# 11_JNZ.net
KiCad netlist of a schematic drawn in EAGLE
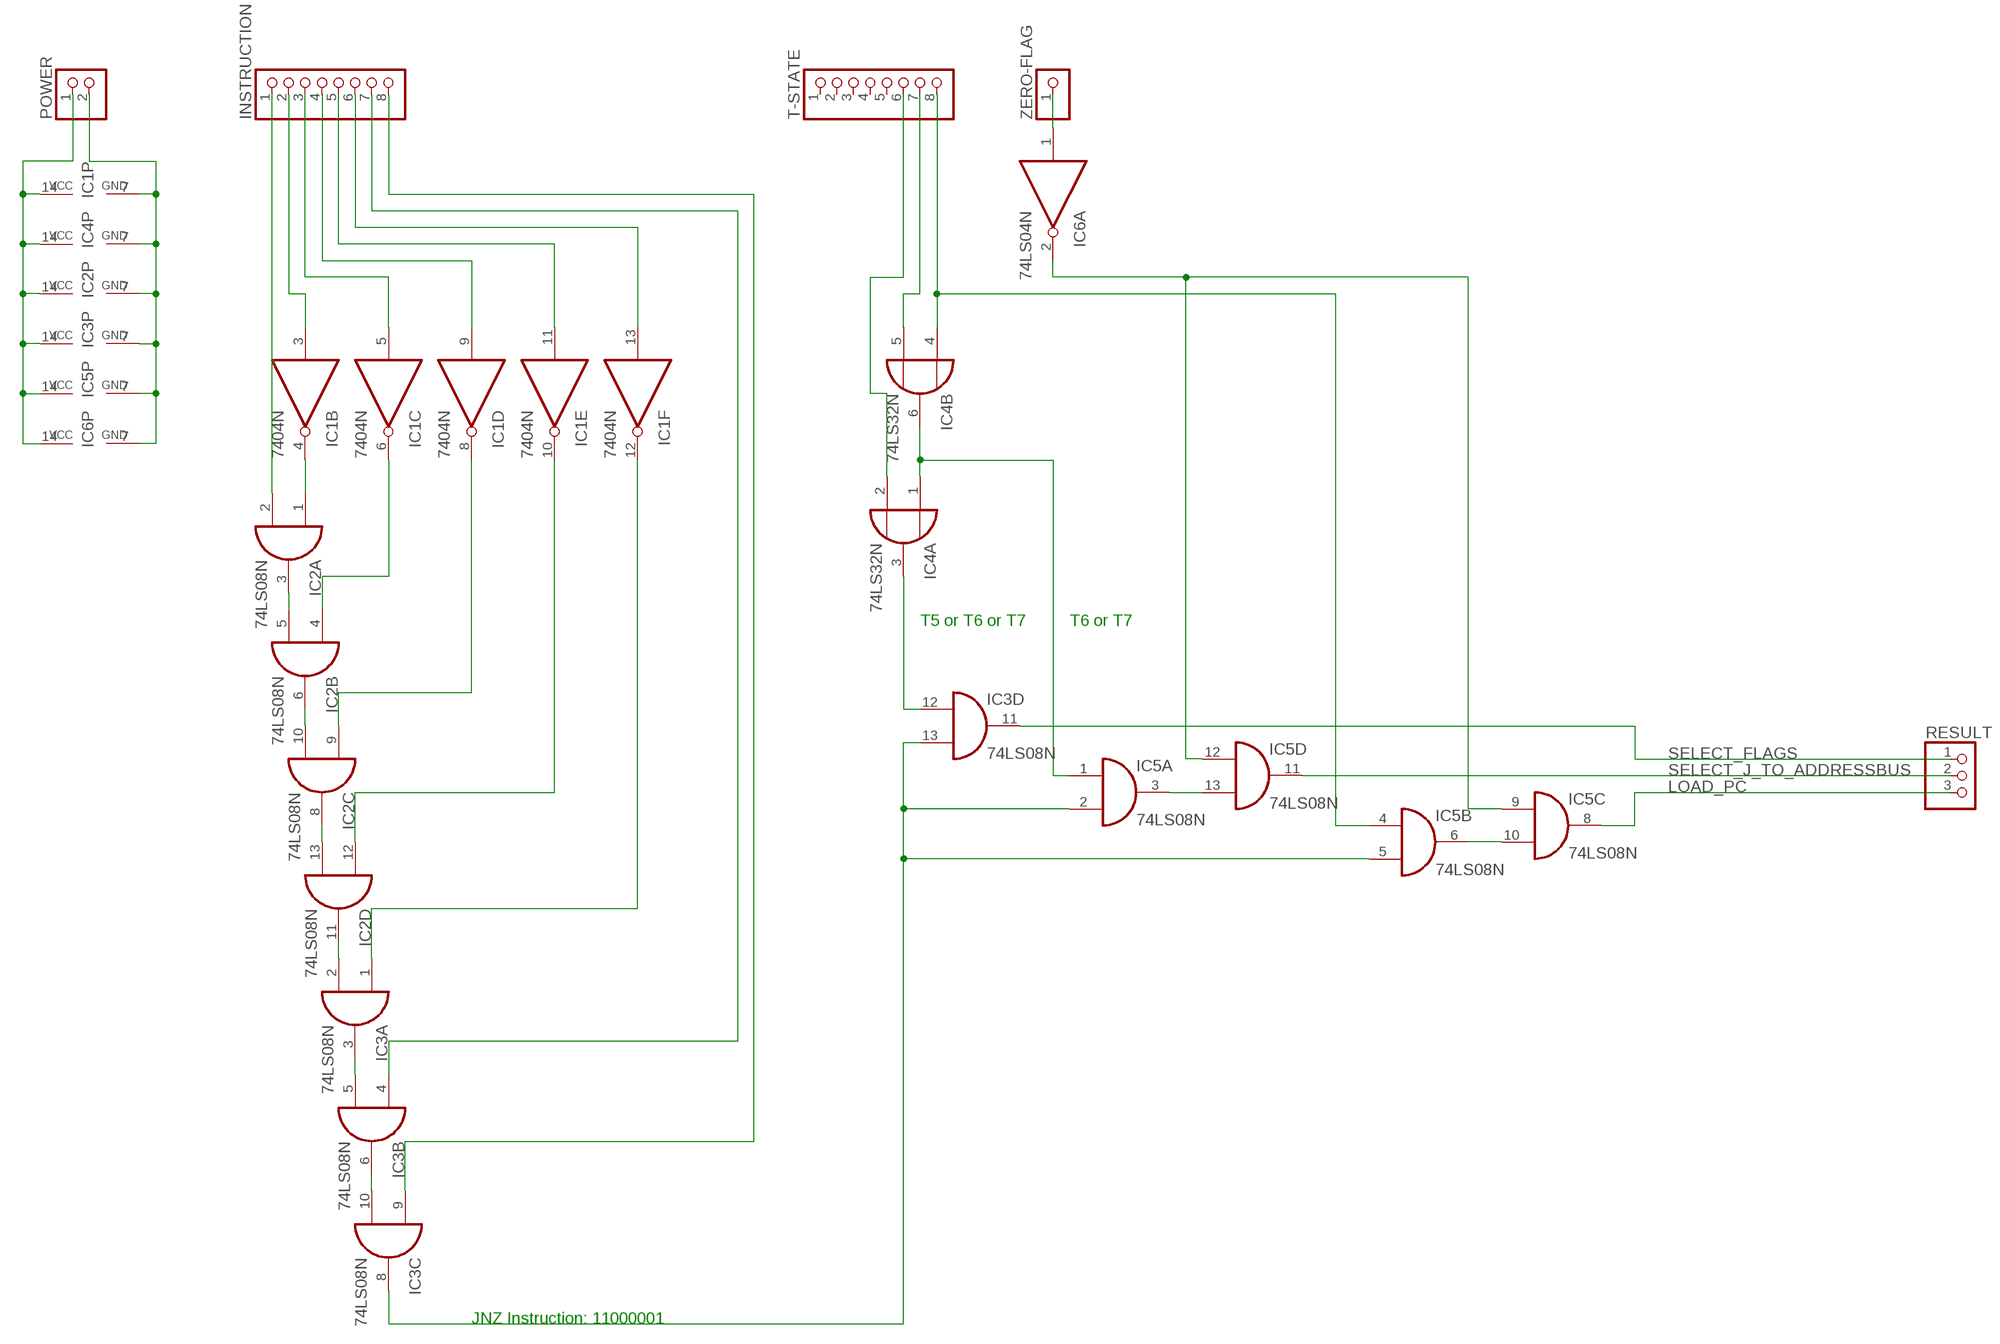
[diagram p0: schematic, sheet 1]

(export (version "E")
  (design (tool "Eeschema 10.0.6"))
  (components
    (comp (ref "IC1")
      (value "7404N")
      (footprint "eagle-import:DIL14")
      (libsource (lib "eagle-import") (part "7404N"))
    )
    (comp (ref "IC2")
      (value "74LS08N")
      (footprint "eagle-import:DIL14")
      (libsource (lib "eagle-import") (part "7408NLS"))
    )
    (comp (ref "IC3")
      (value "74LS08N")
      (footprint "eagle-import:DIL14")
      (libsource (lib "eagle-import") (part "7408NLS"))
    )
    (comp (ref "IC4")
      (value "74LS32N")
      (footprint "eagle-import:DIL14")
      (libsource (lib "eagle-import") (part "7432NLS"))
    )
    (comp (ref "IC5")
      (value "74LS08N")
      (footprint "eagle-import:DIL14")
      (libsource (lib "eagle-import") (part "7408NLS"))
    )
    (comp (ref "IC6")
      (value "74LS04N")
      (footprint "eagle-import:DIL14")
      (libsource (lib "eagle-import") (part "7404NLS"))
    )
    (comp (ref "INSTRUCTION")
      (value "PINHD-1X8")
      (footprint "eagle-import:1X08")
      (libsource (lib "eagle-import") (part "PINHD-1X8"))
    )
    (comp (ref "POWER")
      (value "PINHD-1X2")
      (footprint "eagle-import:1X02")
      (libsource (lib "eagle-import") (part "PINHD-1X2"))
    )
    (comp (ref "RESULT")
      (value "PINHD-1X3")
      (footprint "eagle-import:1X03")
      (libsource (lib "eagle-import") (part "PINHD-1X3"))
    )
    (comp (ref "T-STATE")
      (value "PINHD-1X8")
      (footprint "eagle-import:1X08")
      (libsource (lib "eagle-import") (part "PINHD-1X8"))
    )
    (comp (ref "ZERO-FLAG")
      (value "PINHD-1X1")
      (footprint "eagle-import:1X01")
      (libsource (lib "eagle-import") (part "PINHD-1X1"))
    )
  )
  (nets
    (net (code "1") (name "/LOAD_PC") (class "Default")
      (node (ref "IC5") (pin "8") (pinfunction "O_8") (pintype "output"))
      (node (ref "RESULT") (pin "3") (pinfunction "3_3") (pintype "passive"))
    )
    (net (code "2") (name "/SELECT_FLAGS") (class "Default")
      (node (ref "IC3") (pin "11") (pinfunction "O_11") (pintype "output"))
      (node (ref "RESULT") (pin "1") (pinfunction "1_1") (pintype "passive"))
    )
    (net (code "3") (name "/SELECT_J_TO_ADDRESSBUS") (class "Default")
      (node (ref "IC5") (pin "11") (pinfunction "O_11") (pintype "output"))
      (node (ref "RESULT") (pin "2") (pinfunction "2_2") (pintype "passive"))
    )
    (net (code "4") (name "Net-(IC1B-I)") (class "Default")
      (node (ref "IC1") (pin "3") (pinfunction "I_3") (pintype "input"))
      (node (ref "INSTRUCTION") (pin "2") (pinfunction "2_2") (pintype "passive"))
    )
    (net (code "5") (name "Net-(IC1B-O)") (class "Default")
      (node (ref "IC1") (pin "4") (pinfunction "O_4") (pintype "output"))
      (node (ref "IC2") (pin "1") (pinfunction "I0_1") (pintype "input"))
    )
    (net (code "6") (name "Net-(IC1C-I)") (class "Default")
      (node (ref "IC1") (pin "5") (pinfunction "I_5") (pintype "input"))
      (node (ref "INSTRUCTION") (pin "3") (pinfunction "3_3") (pintype "passive"))
    )
    (net (code "7") (name "Net-(IC1C-O)") (class "Default")
      (node (ref "IC1") (pin "6") (pinfunction "O_6") (pintype "output"))
      (node (ref "IC2") (pin "4") (pinfunction "I0_4") (pintype "input"))
    )
    (net (code "8") (name "Net-(IC1D-I)") (class "Default")
      (node (ref "IC1") (pin "9") (pinfunction "I_9") (pintype "input"))
      (node (ref "INSTRUCTION") (pin "4") (pinfunction "4_4") (pintype "passive"))
    )
    (net (code "9") (name "Net-(IC1D-O)") (class "Default")
      (node (ref "IC1") (pin "8") (pinfunction "O_8") (pintype "output"))
      (node (ref "IC2") (pin "9") (pinfunction "I0_9") (pintype "input"))
    )
    (net (code "10") (name "Net-(IC1E-I)") (class "Default")
      (node (ref "IC1") (pin "11") (pinfunction "I_11") (pintype "input"))
      (node (ref "INSTRUCTION") (pin "5") (pinfunction "5_5") (pintype "passive"))
    )
    (net (code "11") (name "Net-(IC1E-O)") (class "Default")
      (node (ref "IC1") (pin "10") (pinfunction "O_10") (pintype "output"))
      (node (ref "IC2") (pin "12") (pinfunction "I0_12") (pintype "input"))
    )
    (net (code "12") (name "Net-(IC1F-I)") (class "Default")
      (node (ref "IC1") (pin "13") (pinfunction "I_13") (pintype "input"))
      (node (ref "INSTRUCTION") (pin "6") (pinfunction "6_6") (pintype "passive"))
    )
    (net (code "13") (name "Net-(IC1F-O)") (class "Default")
      (node (ref "IC1") (pin "12") (pinfunction "O_12") (pintype "output"))
      (node (ref "IC3") (pin "1") (pinfunction "I0_1") (pintype "input"))
    )
    (net (code "14") (name "Net-(IC1G-GND)") (class "Default")
      (node (ref "IC1") (pin "7") (pinfunction "GND_7") (pintype "power_in"))
      (node (ref "IC2") (pin "7") (pinfunction "GND_7") (pintype "power_in"))
      (node (ref "IC3") (pin "7") (pinfunction "GND_7") (pintype "power_in"))
      (node (ref "IC4") (pin "7") (pinfunction "GND_7") (pintype "power_in"))
      (node (ref "IC5") (pin "7") (pinfunction "GND_7") (pintype "power_in"))
      (node (ref "IC6") (pin "7") (pinfunction "GND_7") (pintype "power_in"))
      (node (ref "POWER") (pin "2") (pinfunction "2_2") (pintype "passive"))
    )
    (net (code "15") (name "Net-(IC1G-VCC)") (class "Default")
      (node (ref "IC1") (pin "14") (pinfunction "VCC_14") (pintype "power_in"))
      (node (ref "IC2") (pin "14") (pinfunction "VCC_14") (pintype "power_in"))
      (node (ref "IC3") (pin "14") (pinfunction "VCC_14") (pintype "power_in"))
      (node (ref "IC4") (pin "14") (pinfunction "VCC_14") (pintype "power_in"))
      (node (ref "IC5") (pin "14") (pinfunction "VCC_14") (pintype "power_in"))
      (node (ref "IC6") (pin "14") (pinfunction "VCC_14") (pintype "power_in"))
      (node (ref "POWER") (pin "1") (pinfunction "1_1") (pintype "passive"))
    )
    (net (code "16") (name "Net-(IC2A-I1)") (class "Default")
      (node (ref "IC2") (pin "2") (pinfunction "I1_2") (pintype "input"))
      (node (ref "INSTRUCTION") (pin "1") (pinfunction "1_1") (pintype "passive"))
    )
    (net (code "17") (name "Net-(IC2A-O)") (class "Default")
      (node (ref "IC2") (pin "3") (pinfunction "O_3") (pintype "output"))
      (node (ref "IC2") (pin "5") (pinfunction "I1_5") (pintype "input"))
    )
    (net (code "18") (name "Net-(IC2B-O)") (class "Default")
      (node (ref "IC2") (pin "10") (pinfunction "I1_10") (pintype "input"))
      (node (ref "IC2") (pin "6") (pinfunction "O_6") (pintype "output"))
    )
    (net (code "19") (name "Net-(IC2C-O)") (class "Default")
      (node (ref "IC2") (pin "13") (pinfunction "I1_13") (pintype "input"))
      (node (ref "IC2") (pin "8") (pinfunction "O_8") (pintype "output"))
    )
    (net (code "20") (name "Net-(IC2D-O)") (class "Default")
      (node (ref "IC2") (pin "11") (pinfunction "O_11") (pintype "output"))
      (node (ref "IC3") (pin "2") (pinfunction "I1_2") (pintype "input"))
    )
    (net (code "21") (name "Net-(IC3A-O)") (class "Default")
      (node (ref "IC3") (pin "3") (pinfunction "O_3") (pintype "output"))
      (node (ref "IC3") (pin "5") (pinfunction "I1_5") (pintype "input"))
    )
    (net (code "22") (name "Net-(IC3B-I0)") (class "Default")
      (node (ref "IC3") (pin "4") (pinfunction "I0_4") (pintype "input"))
      (node (ref "INSTRUCTION") (pin "7") (pinfunction "7_7") (pintype "passive"))
    )
    (net (code "23") (name "Net-(IC3B-O)") (class "Default")
      (node (ref "IC3") (pin "10") (pinfunction "I1_10") (pintype "input"))
      (node (ref "IC3") (pin "6") (pinfunction "O_6") (pintype "output"))
    )
    (net (code "24") (name "Net-(IC3C-I0)") (class "Default")
      (node (ref "IC3") (pin "9") (pinfunction "I0_9") (pintype "input"))
      (node (ref "INSTRUCTION") (pin "8") (pinfunction "8_8") (pintype "passive"))
    )
    (net (code "25") (name "Net-(IC3C-O)") (class "Default")
      (node (ref "IC3") (pin "13") (pinfunction "I1_13") (pintype "input"))
      (node (ref "IC3") (pin "8") (pinfunction "O_8") (pintype "output"))
      (node (ref "IC5") (pin "2") (pinfunction "I1_2") (pintype "input"))
      (node (ref "IC5") (pin "5") (pinfunction "I1_5") (pintype "input"))
    )
    (net (code "26") (name "Net-(IC3D-I0)") (class "Default")
      (node (ref "IC3") (pin "12") (pinfunction "I0_12") (pintype "input"))
      (node (ref "IC4") (pin "3") (pinfunction "O_3") (pintype "output"))
    )
    (net (code "27") (name "Net-(IC4A-I0)") (class "Default")
      (node (ref "IC4") (pin "1") (pinfunction "I0_1") (pintype "input"))
      (node (ref "IC4") (pin "6") (pinfunction "O_6") (pintype "output"))
      (node (ref "IC5") (pin "1") (pinfunction "I0_1") (pintype "input"))
    )
    (net (code "28") (name "Net-(IC4A-I1)") (class "Default")
      (node (ref "IC4") (pin "2") (pinfunction "I1_2") (pintype "input"))
      (node (ref "T-STATE") (pin "6") (pinfunction "6_6") (pintype "passive"))
    )
    (net (code "29") (name "Net-(IC4B-I0)") (class "Default")
      (node (ref "IC4") (pin "4") (pinfunction "I0_4") (pintype "input"))
      (node (ref "IC5") (pin "4") (pinfunction "I0_4") (pintype "input"))
      (node (ref "T-STATE") (pin "8") (pinfunction "8_8") (pintype "passive"))
    )
    (net (code "30") (name "Net-(IC4B-I1)") (class "Default")
      (node (ref "IC4") (pin "5") (pinfunction "I1_5") (pintype "input"))
      (node (ref "T-STATE") (pin "7") (pinfunction "7_7") (pintype "passive"))
    )
    (net (code "31") (name "Net-(IC5A-O)") (class "Default")
      (node (ref "IC5") (pin "13") (pinfunction "I1_13") (pintype "input"))
      (node (ref "IC5") (pin "3") (pinfunction "O_3") (pintype "output"))
    )
    (net (code "32") (name "Net-(IC5B-O)") (class "Default")
      (node (ref "IC5") (pin "10") (pinfunction "I1_10") (pintype "input"))
      (node (ref "IC5") (pin "6") (pinfunction "O_6") (pintype "output"))
    )
    (net (code "33") (name "Net-(IC5C-I0)") (class "Default")
      (node (ref "IC5") (pin "12") (pinfunction "I0_12") (pintype "input"))
      (node (ref "IC5") (pin "9") (pinfunction "I0_9") (pintype "input"))
      (node (ref "IC6") (pin "2") (pinfunction "O_2") (pintype "output"))
    )
    (net (code "34") (name "Net-(IC6A-I)") (class "Default")
      (node (ref "IC6") (pin "1") (pinfunction "I_1") (pintype "input"))
      (node (ref "ZERO-FLAG") (pin "1") (pinfunction "1_1") (pintype "passive"))
    )
    (net (code "35") (name "unconnected-(T-STATE-Pad1)") (class "Default")
      (node (ref "T-STATE") (pin "1") (pinfunction "1_1") (pintype "passive"))
    )
    (net (code "36") (name "unconnected-(T-STATE-Pad2)") (class "Default")
      (node (ref "T-STATE") (pin "2") (pinfunction "2_2") (pintype "passive"))
    )
    (net (code "37") (name "unconnected-(T-STATE-Pad3)") (class "Default")
      (node (ref "T-STATE") (pin "3") (pinfunction "3_3") (pintype "passive"))
    )
    (net (code "38") (name "unconnected-(T-STATE-Pad4)") (class "Default")
      (node (ref "T-STATE") (pin "4") (pinfunction "4_4") (pintype "passive"))
    )
    (net (code "39") (name "unconnected-(T-STATE-Pad5)") (class "Default")
      (node (ref "T-STATE") (pin "5") (pinfunction "5_5") (pintype "passive"))
    )
  )
)
